# ADC.net
KiCad netlist of a schematic drawn in Altium Designer
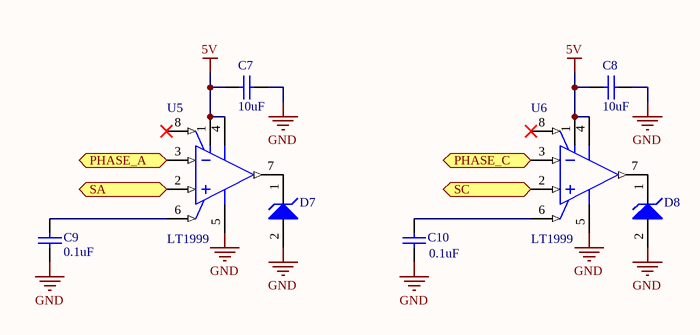
[diagram p0: ADC.SchDoc]

(export (version "E")
  (design (tool "Eeschema 10.0.6"))
  (components
    (comp (ref "C7")
      (value "10uF")
      (footprint "CAPC0603(1608)100_M")
      (description "CAP 10uF 6.3V Â±10% 0603 (1608 Metric) Thickness 1mm SMD")
      (fields (field (name "TOLERANCE") "Â±10%"))
      (libsource (lib "Altium Content Vault") (part "CMP-1035-02796-1"))
    )
    (comp (ref "C8")
      (value "10uF")
      (footprint "CAPC0603(1608)100_N")
      (description "CAP 10uF 6.3V Â±20% 0603 (1608 Metric) Thickness 1mm SMD")
      (fields (field (name "TOLERANCE") "Â±20%"))
      (libsource (lib "Altium Content Vault") (part "CMP-1035-02797-1"))
    )
    (comp (ref "C9")
      (value "0.1uF")
      (footprint "CAPC0603(1608)100_L")
      (description "CAP 100nF 6.3V Â±20% 0603 (1608 Metric) Thickness 1mm SMD")
      (fields (field (name "TOLERANCE") "Â±20%"))
      (libsource (lib "Altium Content Vault") (part "CMP-1035-02577-1"))
    )
    (comp (ref "C10")
      (value "0.1uF")
      (footprint "CAPC0603(1608)100_L")
      (description "CAP 100nF 6.3V Â±20% 0603 (1608 Metric) Thickness 1mm SMD")
      (fields (field (name "TOLERANCE") "Â±20%"))
      (libsource (lib "Altium Content Vault") (part "CMP-1035-02577-1"))
    )
    (comp (ref "D7")
      (value "~")
      (footprint "ONSC-SOD-323-2-477-02_V")
      (description "Zener Voltage Regulator, 300 mW, Tight Tolerance Portfolio, 2-Pin SOD-323, Pb-Free, Tape and Reel")
      (fields (field (name "PARTNUMBER") "MM3Z3V3ST1G") (field (name "MANUFACTURER") "On Semiconductor"))
      (libsource (lib "Altium Inc") (part "ONSC-K1A2-2"))
    )
    (comp (ref "D8")
      (value "~")
      (footprint "ONSC-SOD-323-2-477-02_V")
      (description "Zener Voltage Regulator, 300 mW, Tight Tolerance Portfolio, 2-Pin SOD-323, Pb-Free, Tape and Reel")
      (fields (field (name "PARTNUMBER") "MM3Z3V3ST1G") (field (name "MANUFACTURER") "On Semiconductor"))
      (libsource (lib "Altium Content Vault") (part "CMP-1060-00652-1"))
    )
    (comp (ref "U5")
      (value "LT1999")
      (footprint "LT-MS8-8_N")
      (fields
        (field (name "MANUFACTURER") "Linear Technology")
        (field (name "PARTNUMBER") "LT1999HMS8-20#TRPBF")
        (field (name "LINEAR TECHNOLOGY PART NUMBER") "LT1999-20")
      )
      (libsource (lib "Altium Content Vault") (part "LT-LT1999-20-MS8-8"))
    )
    (comp (ref "U6")
      (value "LT1999")
      (footprint "LT-MS8-8_N")
      (fields
        (field (name "MANUFACTURER") "Linear Technology")
        (field (name "PARTNUMBER") "LT1999HMS8-20#TRPBF")
        (field (name "LINEAR TECHNOLOGY PART NUMBER") "LT1999-20")
      )
      (libsource (lib "Altium Content Vault") (part "LT-LT1999-20-MS8-8"))
    )
  )
  (nets
    (net (code "1") (name "/PHASE_A") (class "Default")
      (node (ref "U5") (pin "3") (pinfunction "-IN_3") (pintype "input"))
    )
    (net (code "2") (name "/PHASE_C") (class "Default")
      (node (ref "U6") (pin "3") (pinfunction "-IN_3") (pintype "input"))
    )
    (net (code "3") (name "/SA") (class "Default")
      (node (ref "U5") (pin "2") (pinfunction "+IN_2") (pintype "input"))
    )
    (net (code "4") (name "/SC") (class "Default")
      (node (ref "U6") (pin "2") (pinfunction "+IN_2") (pintype "input"))
    )
    (net (code "5") (name "5V") (class "Default")
      (node (ref "C7") (pin "1") (pinfunction "1_1") (pintype "passive"))
      (node (ref "C8") (pin "1") (pinfunction "1_1") (pintype "passive"))
      (node (ref "U5") (pin "1") (pinfunction "V+_1") (pintype "power_in"))
      (node (ref "U5") (pin "4") (pinfunction "V+_4") (pintype "power_in"))
      (node (ref "U6") (pin "1") (pinfunction "V+_1") (pintype "power_in"))
      (node (ref "U6") (pin "4") (pinfunction "V+_4") (pintype "power_in"))
    )
    (net (code "6") (name "GND") (class "Default")
      (node (ref "C10") (pin "1") (pinfunction "1_1") (pintype "passive"))
      (node (ref "C7") (pin "2") (pinfunction "2_2") (pintype "passive"))
      (node (ref "C8") (pin "2") (pinfunction "2_2") (pintype "passive"))
      (node (ref "C9") (pin "1") (pinfunction "1_1") (pintype "passive"))
      (node (ref "D7") (pin "2") (pinfunction "A_2") (pintype "passive"))
      (node (ref "D8") (pin "2") (pinfunction "A_2") (pintype "passive"))
      (node (ref "U5") (pin "5") (pinfunction "GND_5") (pintype "power_in"))
      (node (ref "U6") (pin "5") (pinfunction "GND_5") (pintype "power_in"))
    )
    (net (code "7") (name "Net-(D7-K)") (class "Default")
      (node (ref "D7") (pin "1") (pinfunction "K_1") (pintype "passive"))
      (node (ref "U5") (pin "7") (pinfunction "OUT_7") (pintype "output"))
    )
    (net (code "8") (name "Net-(D8-K)") (class "Default")
      (node (ref "D8") (pin "1") (pinfunction "K_1") (pintype "passive"))
      (node (ref "U6") (pin "7") (pinfunction "OUT_7") (pintype "output"))
    )
    (net (code "9") (name "Net-(U5-REF)") (class "Default")
      (node (ref "C9") (pin "2") (pinfunction "2_2") (pintype "passive"))
      (node (ref "U5") (pin "6") (pinfunction "REF_6") (pintype "input"))
    )
    (net (code "10") (name "Net-(U6-REF)") (class "Default")
      (node (ref "C10") (pin "2") (pinfunction "2_2") (pintype "passive"))
      (node (ref "U6") (pin "6") (pinfunction "REF_6") (pintype "input"))
    )
    (net (code "11") (name "unconnected-(U5-~{SHDN}-Pad8)") (class "Default")
      (node (ref "U5") (pin "8") (pinfunction "~{SHDN}_8") (pintype "input+no_connect"))
    )
    (net (code "12") (name "unconnected-(U6-~{SHDN}-Pad8)") (class "Default")
      (node (ref "U6") (pin "8") (pinfunction "~{SHDN}_8") (pintype "input+no_connect"))
    )
  )
)
